# GR740.net
KiCad netlist of a schematic drawn in Altium Designer
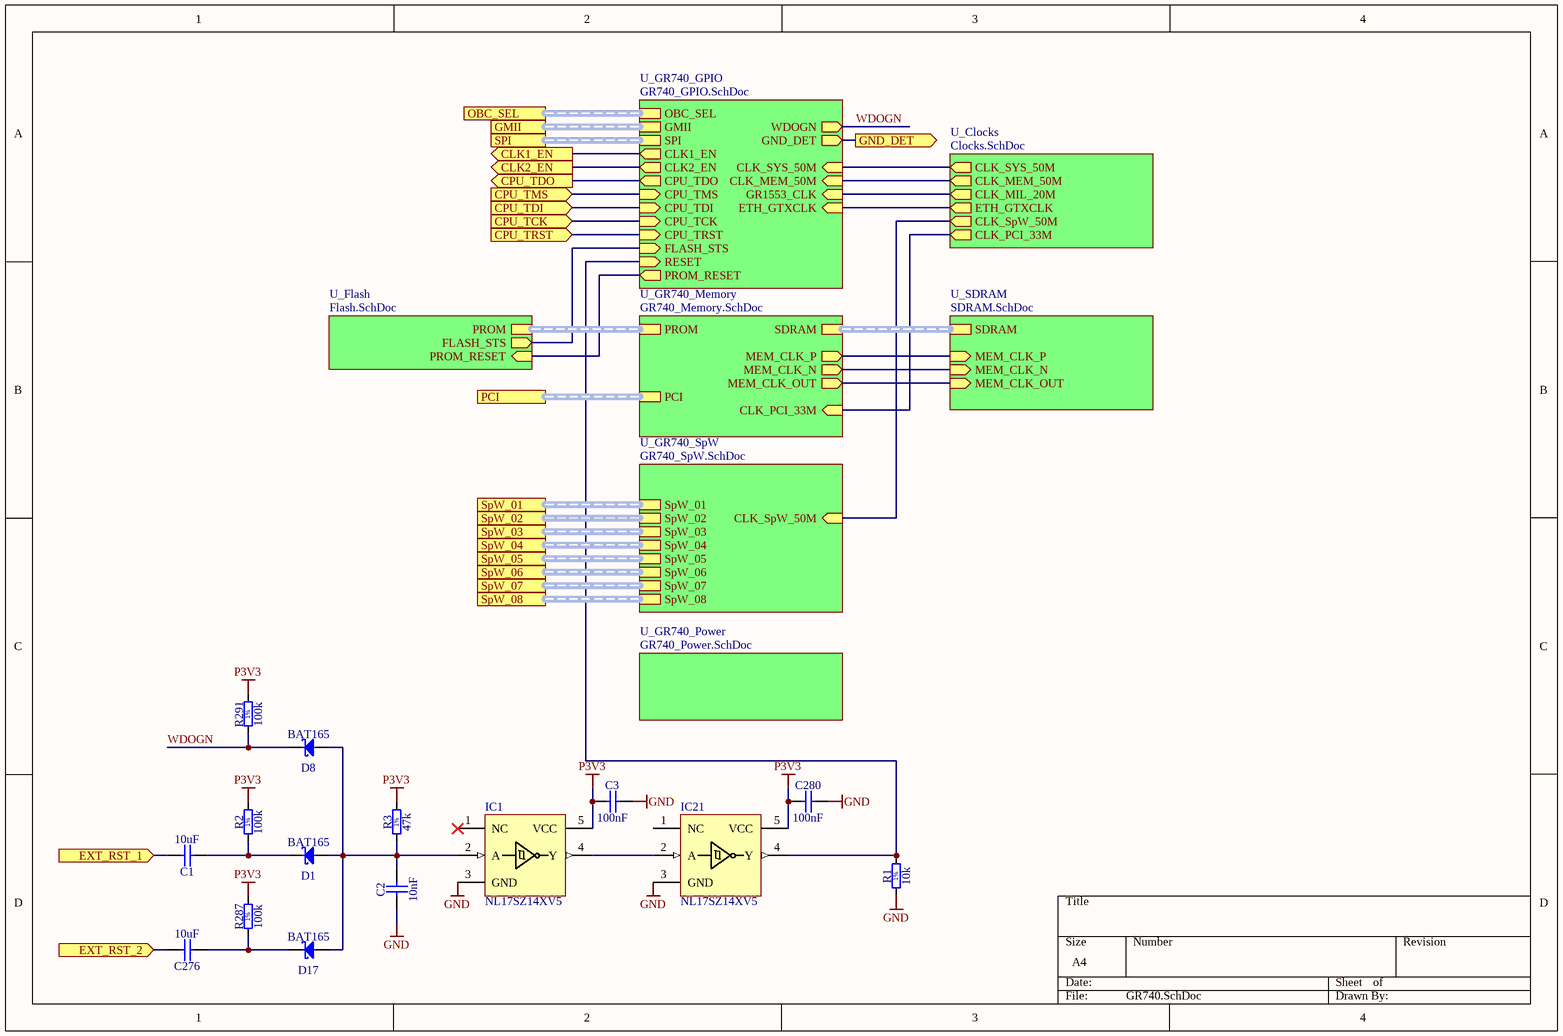
[diagram p0: GR740.SchDoc]

(export (version "E")
  (design (tool "Eeschema 10.0.6"))
  (components
    (comp (ref "C1")
      (value "10uF")
      (footprint "CAPC1608X80N")
      (description "Non-polarised capacitor")
      (fields
        (field (name "PART NUMBER") "CC0603_10UF_16V_20%_X5R")
        (field (name "VOLTAGE") "16V")
        (field (name "AUTHOR") "CERN DEM MR")
      )
      (libsource (lib "Capacitors") (part "Capacitor - non polarized"))
    )
    (comp (ref "C2")
      (value "10nF")
      (footprint "CAPC1005X55N")
      (description "Non-polarised capacitor")
      (fields
        (field (name "PART NUMBER") "CC0402_10NF_50V_10%_X7R")
        (field (name "VOLTAGE") "50V")
        (field (name "AUTHOR") "CERN DEM MR")
      )
      (libsource (lib "Capacitors") (part "Capacitor - non polarized"))
    )
    (comp (ref "C3")
      (value "100nF")
      (footprint "CAPC1005X55N")
      (description "Non-polarised capacitor")
      (fields
        (field (name "PART NUMBER") "CC0402_100NF_25V_10%_X7R_YUDEN_TMK105B7104KVHF")
        (field (name "VOLTAGE") "25V")
        (field (name "AUTHOR") "CERN DEM JLC")
      )
      (libsource (lib "Capacitors") (part "Capacitor - non polarized"))
    )
    (comp (ref "C276")
      (value "10uF")
      (footprint "CAPC1608X80N")
      (description "Non-polarised capacitor")
      (fields
        (field (name "PART NUMBER") "CC0603_10UF_16V_20%_X5R")
        (field (name "VOLTAGE") "16V")
        (field (name "AUTHOR") "CERN DEM MR")
      )
      (libsource (lib "Capacitors") (part "Capacitor - non polarized"))
    )
    (comp (ref "C280")
      (value "100nF")
      (footprint "CAPC1005X55N")
      (description "Non-polarised capacitor")
      (fields
        (field (name "PART NUMBER") "CC0402_100NF_25V_10%_X7R_YUDEN_TMK105B7104KVHF")
        (field (name "VOLTAGE") "25V")
        (field (name "AUTHOR") "CERN DEM JLC")
      )
      (libsource (lib "Capacitors") (part "Capacitor - non polarized"))
    )
    (comp (ref "D1")
      (value "BAT165")
      (footprint "SOD2512X110N")
      (description "Schottky Diode")
      (fields
        (field (name "VOLTAGE") "40V")
        (field (name "POWER") "750mA")
        (field (name "AUTHOR") "CERN DEM JLC")
      )
      (libsource (lib "ICs And Semiconductors") (part "Diode Schottky"))
    )
    (comp (ref "D8")
      (value "BAT165")
      (footprint "SOD2512X110N")
      (description "Schottky Diode")
      (fields
        (field (name "VOLTAGE") "40V")
        (field (name "POWER") "750mA")
        (field (name "AUTHOR") "CERN DEM JLC")
      )
      (libsource (lib "ICs And Semiconductors") (part "Diode Schottky"))
    )
    (comp (ref "D17")
      (value "BAT165")
      (footprint "SOD2512X110N")
      (description "Schottky Diode")
      (fields
        (field (name "VOLTAGE") "40V")
        (field (name "POWER") "750mA")
        (field (name "AUTHOR") "CERN DEM JLC")
      )
      (libsource (lib "ICs And Semiconductors") (part "Diode Schottky"))
    )
    (comp (ref "IC1")
      (value "NL17SZ14XV5")
      (footprint "SOT50P160X60-5N")
      (description "Single inverter with schmitt trigger")
      (fields (field (name "MANUFACTURER") "On Semiconductor"))
      (libsource (lib "ICs_And_Semiconductors") (part "NL17SZ14XV5"))
    )
    (comp (ref "IC21")
      (value "NL17SZ14XV5")
      (footprint "SOT50P160X60-5N")
      (description "Single inverter with schmitt trigger")
      (fields (field (name "MANUFACTURER") "On Semiconductor"))
      (libsource (lib "ICs_And_Semiconductors") (part "NL17SZ14XV5"))
    )
    (comp (ref "R1")
      (value "10k")
      (footprint "RESC1005X40N")
      (description "Resistor - 1%")
      (fields
        (field (name "PART NUMBER") "R0402_10K_1%_0.0625W_100PPM")
        (field (name "POWER") "0.0625W")
        (field (name "AUTHOR") "CERN DEM JLC")
      )
      (libsource (lib "Resistors") (part "Resistor - 1%"))
    )
    (comp (ref "R2")
      (value "100k")
      (footprint "RESC1005X40N")
      (description "Resistor - 1%")
      (fields
        (field (name "PART NUMBER") "R0402_100K_1%_0.0625W_100PPM")
        (field (name "POWER") "0.0625W")
        (field (name "AUTHOR") "CERN DEM JLC")
      )
      (libsource (lib "Resistors") (part "Resistor - 1%"))
    )
    (comp (ref "R3")
      (value "47k")
      (footprint "RESC1005X40N")
      (description "Resistor - 1%")
      (fields
        (field (name "PART NUMBER") "R0402_47K_1%_0.0625W_100PPM")
        (field (name "POWER") "0.0625W")
        (field (name "AUTHOR") "CERN DEM JLC")
      )
      (libsource (lib "Resistors") (part "Resistor - 1%"))
    )
    (comp (ref "R287")
      (value "100k")
      (footprint "RESC1005X40N")
      (description "Resistor - 1%")
      (fields
        (field (name "PART NUMBER") "R0402_100K_1%_0.0625W_100PPM")
        (field (name "POWER") "0.0625W")
        (field (name "AUTHOR") "CERN DEM JLC")
      )
      (libsource (lib "Resistors") (part "Resistor - 1%"))
    )
    (comp (ref "R291")
      (value "100k")
      (footprint "RESC1005X40N")
      (description "Resistor - 1%")
      (fields
        (field (name "PART NUMBER") "R0402_100K_1%_0.0625W_100PPM")
        (field (name "POWER") "0.0625W")
        (field (name "AUTHOR") "CERN DEM JLC")
      )
      (libsource (lib "Resistors") (part "Resistor - 1%"))
    )
  )
  (nets
    (net (code "26") (name "/EXT_RST_1") (class "Default")
      (node (ref "C1") (pin "2") (pinfunction "2_2") (pintype "passive"))
    )
    (net (code "27") (name "/EXT_RST_2") (class "Default")
      (node (ref "C276") (pin "2") (pinfunction "2_2") (pintype "passive"))
    )
    (net (code "38") (name "/RESET") (class "Default")
      (node (ref "IC21") (pin "4") (pinfunction "Y_4") (pintype "output"))
      (node (ref "R1") (pin "2") (pinfunction "2_2") (pintype "passive"))
    )
    (net (code "49") (name "/WDOGN") (class "Default")
      (node (ref "D8") (pin "1") (pinfunction "C_1") (pintype "passive"))
      (node (ref "R291") (pin "1") (pinfunction "1_1") (pintype "passive"))
    )
    (net (code "50") (name "GND") (class "Default")
      (node (ref "C2") (pin "1") (pinfunction "1_1") (pintype "passive"))
      (node (ref "C280") (pin "2") (pinfunction "2_2") (pintype "passive"))
      (node (ref "C3") (pin "2") (pinfunction "2_2") (pintype "passive"))
      (node (ref "IC1") (pin "3") (pinfunction "GND_3") (pintype "power_in"))
      (node (ref "IC21") (pin "3") (pinfunction "GND_3") (pintype "power_in"))
      (node (ref "R1") (pin "1") (pinfunction "1_1") (pintype "passive"))
    )
    (net (code "51") (name "Net-(D1-A)") (class "Default")
      (node (ref "C2") (pin "2") (pinfunction "2_2") (pintype "passive"))
      (node (ref "D1") (pin "2") (pinfunction "A_2") (pintype "passive"))
      (node (ref "D17") (pin "2") (pinfunction "A_2") (pintype "passive"))
      (node (ref "D8") (pin "2") (pinfunction "A_2") (pintype "passive"))
      (node (ref "IC1") (pin "2") (pinfunction "A_2") (pintype "input"))
      (node (ref "R3") (pin "1") (pinfunction "1_1") (pintype "passive"))
    )
    (net (code "52") (name "Net-(D1-C)") (class "Default")
      (node (ref "C1") (pin "1") (pinfunction "1_1") (pintype "passive"))
      (node (ref "D1") (pin "1") (pinfunction "C_1") (pintype "passive"))
      (node (ref "R2") (pin "1") (pinfunction "1_1") (pintype "passive"))
    )
    (net (code "53") (name "Net-(D17-C)") (class "Default")
      (node (ref "C276") (pin "1") (pinfunction "1_1") (pintype "passive"))
      (node (ref "D17") (pin "1") (pinfunction "C_1") (pintype "passive"))
      (node (ref "R287") (pin "1") (pinfunction "1_1") (pintype "passive"))
    )
    (net (code "54") (name "Net-(IC1-Y)") (class "Default")
      (node (ref "IC1") (pin "4") (pinfunction "Y_4") (pintype "output"))
      (node (ref "IC21") (pin "2") (pinfunction "A_2") (pintype "input"))
    )
    (net (code "55") (name "P3V3") (class "Default")
      (node (ref "C280") (pin "1") (pinfunction "1_1") (pintype "passive"))
      (node (ref "C3") (pin "1") (pinfunction "1_1") (pintype "passive"))
      (node (ref "IC1") (pin "5") (pinfunction "VCC_5") (pintype "power_in"))
      (node (ref "IC21") (pin "5") (pinfunction "VCC_5") (pintype "power_in"))
      (node (ref "R2") (pin "2") (pinfunction "2_2") (pintype "passive"))
      (node (ref "R287") (pin "2") (pinfunction "2_2") (pintype "passive"))
      (node (ref "R291") (pin "2") (pinfunction "2_2") (pintype "passive"))
      (node (ref "R3") (pin "2") (pinfunction "2_2") (pintype "passive"))
    )
    (net (code "56") (name "unconnected-(IC1-NC-Pad1)") (class "Default")
      (node (ref "IC1") (pin "1") (pinfunction "NC_1") (pintype "passive+no_connect"))
    )
    (net (code "57") (name "unconnected-(IC21-NC-Pad1)") (class "Default")
      (node (ref "IC21") (pin "1") (pinfunction "NC_1") (pintype "passive"))
    )
  )
)
